# filters.net
KiCad netlist of a schematic drawn in Altium Designer
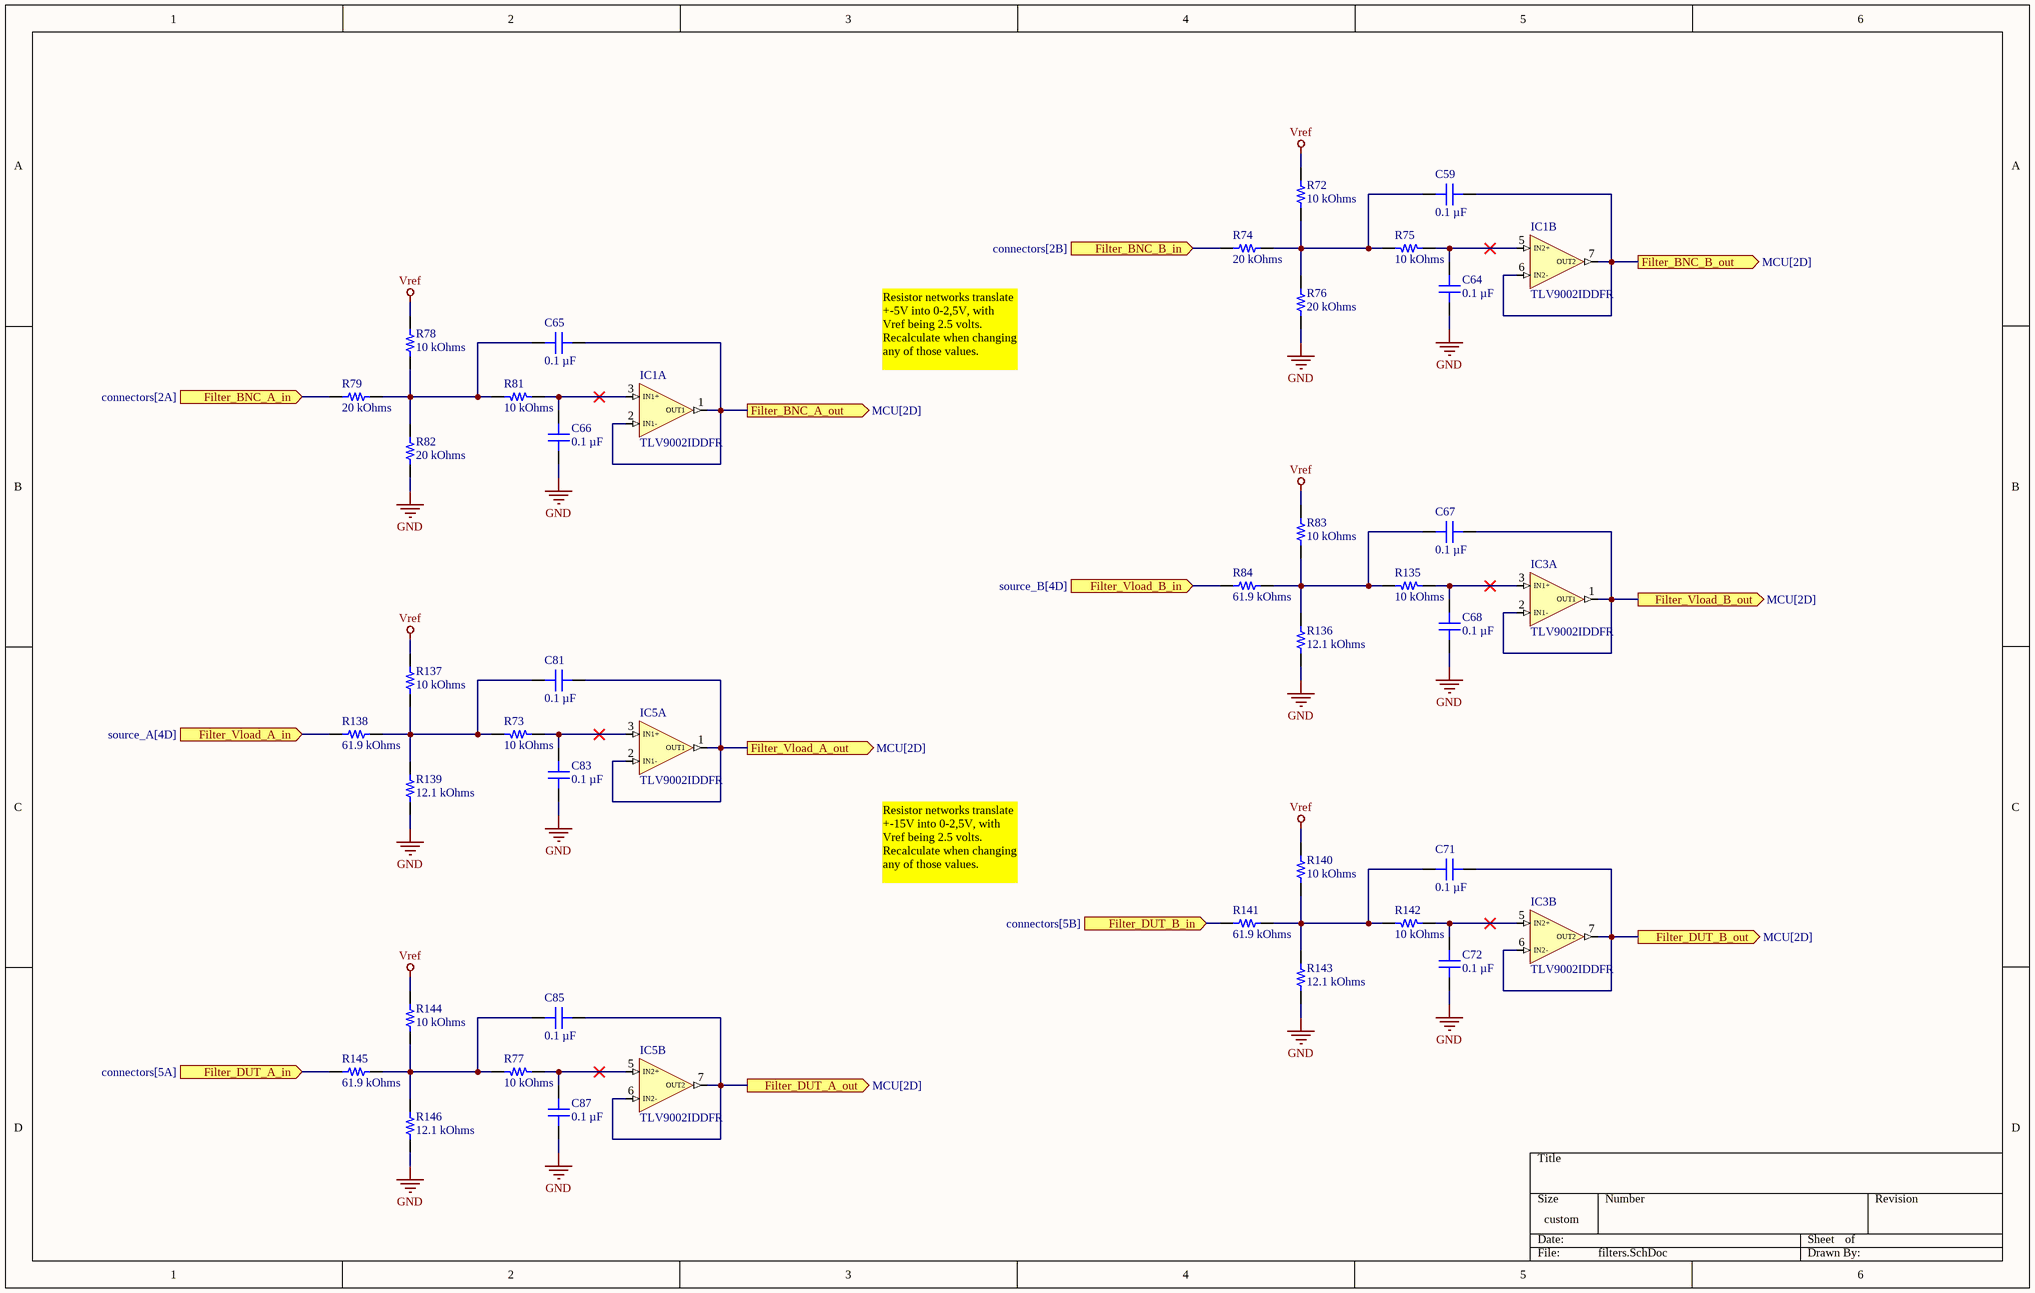
[diagram p0: filters.SchDoc]

(export (version "E")
  (design (tool "Eeschema 10.0.6"))
  (components
    (comp (ref "C59")
      (value "0.1 µF")
      (footprint "CAP 1206_3216 - 0.8MM")
      (description "CAP CER 0.1UF 50V X7R 1206")
      (fields
        (field (name "PART NUMBER") "885012208087")
        (field (name "CAPACITANCE") "0.1 µF")
        (field (name "MANUFACTURER") "Würth Elektronik")
      )
      (libsource (lib "Celestial Altium Library - altium_library") (part "Capacitor"))
    )
    (comp (ref "C64")
      (value "0.1 µF")
      (footprint "CAP 1206_3216 - 0.8MM")
      (description "CAP CER 0.1UF 50V X7R 1206")
      (fields
        (field (name "PART NUMBER") "885012208087")
        (field (name "CAPACITANCE") "0.1 µF")
        (field (name "MANUFACTURER") "Würth Elektronik")
      )
      (libsource (lib "Celestial Altium Library - altium_library") (part "Capacitor"))
    )
    (comp (ref "C65")
      (value "0.1 µF")
      (footprint "CAP 1206_3216 - 0.8MM")
      (description "CAP CER 0.1UF 50V X7R 1206")
      (fields
        (field (name "PART NUMBER") "885012208087")
        (field (name "CAPACITANCE") "0.1 µF")
        (field (name "MANUFACTURER") "Würth Elektronik")
      )
      (libsource (lib "Celestial Altium Library - altium_library") (part "Capacitor"))
    )
    (comp (ref "C66")
      (value "0.1 µF")
      (footprint "CAP 1206_3216 - 0.8MM")
      (description "CAP CER 0.1UF 50V X7R 1206")
      (fields
        (field (name "PART NUMBER") "885012208087")
        (field (name "CAPACITANCE") "0.1 µF")
        (field (name "MANUFACTURER") "Würth Elektronik")
      )
      (libsource (lib "Celestial Altium Library - altium_library") (part "Capacitor"))
    )
    (comp (ref "C67")
      (value "0.1 µF")
      (footprint "CAP 1206_3216 - 0.8MM")
      (description "CAP CER 0.1UF 50V X7R 1206")
      (fields
        (field (name "PART NUMBER") "885012208087")
        (field (name "CAPACITANCE") "0.1 µF")
        (field (name "MANUFACTURER") "Würth Elektronik")
      )
      (libsource (lib "Celestial Altium Library - altium_library") (part "Capacitor"))
    )
    (comp (ref "C68")
      (value "0.1 µF")
      (footprint "CAP 1206_3216 - 0.8MM")
      (description "CAP CER 0.1UF 50V X7R 1206")
      (fields
        (field (name "PART NUMBER") "885012208087")
        (field (name "CAPACITANCE") "0.1 µF")
        (field (name "MANUFACTURER") "Würth Elektronik")
      )
      (libsource (lib "Celestial Altium Library - altium_library") (part "Capacitor"))
    )
    (comp (ref "C71")
      (value "0.1 µF")
      (footprint "CAP 1206_3216 - 0.8MM")
      (description "CAP CER 0.1UF 50V X7R 1206")
      (fields
        (field (name "PART NUMBER") "885012208087")
        (field (name "CAPACITANCE") "0.1 µF")
        (field (name "MANUFACTURER") "Würth Elektronik")
      )
      (libsource (lib "Celestial Altium Library - altium_library") (part "Capacitor"))
    )
    (comp (ref "C72")
      (value "0.1 µF")
      (footprint "CAP 1206_3216 - 0.8MM")
      (description "CAP CER 0.1UF 50V X7R 1206")
      (fields
        (field (name "PART NUMBER") "885012208087")
        (field (name "CAPACITANCE") "0.1 µF")
        (field (name "MANUFACTURER") "Würth Elektronik")
      )
      (libsource (lib "Celestial Altium Library - altium_library") (part "Capacitor"))
    )
    (comp (ref "C81")
      (value "0.1 µF")
      (footprint "CAP 1206_3216 - 0.8MM")
      (description "CAP CER 0.1UF 50V X7R 1206")
      (fields
        (field (name "PART NUMBER") "885012208087")
        (field (name "CAPACITANCE") "0.1 µF")
        (field (name "MANUFACTURER") "Würth Elektronik")
      )
      (libsource (lib "Celestial Altium Library - altium_library") (part "Capacitor"))
    )
    (comp (ref "C83")
      (value "0.1 µF")
      (footprint "CAP 1206_3216 - 0.8MM")
      (description "CAP CER 0.1UF 50V X7R 1206")
      (fields
        (field (name "PART NUMBER") "885012208087")
        (field (name "CAPACITANCE") "0.1 µF")
        (field (name "MANUFACTURER") "Würth Elektronik")
      )
      (libsource (lib "Celestial Altium Library - altium_library") (part "Capacitor"))
    )
    (comp (ref "C85")
      (value "0.1 µF")
      (footprint "CAP 1206_3216 - 0.8MM")
      (description "CAP CER 0.1UF 50V X7R 1206")
      (fields
        (field (name "PART NUMBER") "885012208087")
        (field (name "CAPACITANCE") "0.1 µF")
        (field (name "MANUFACTURER") "Würth Elektronik")
      )
      (libsource (lib "Celestial Altium Library - altium_library") (part "Capacitor"))
    )
    (comp (ref "C87")
      (value "0.1 µF")
      (footprint "CAP 1206_3216 - 0.8MM")
      (description "CAP CER 0.1UF 50V X7R 1206")
      (fields
        (field (name "PART NUMBER") "885012208087")
        (field (name "CAPACITANCE") "0.1 µF")
        (field (name "MANUFACTURER") "Würth Elektronik")
      )
      (libsource (lib "Celestial Altium Library - altium_library") (part "Capacitor"))
    )
    (comp (ref "IC1")
      (value "TLV9002IDDFR")
      (footprint "SOT65P280X110-8N")
      (description "Integrated Circuit")
      (fields (field (name "MOUSER PART NUMBER") "595-TLV9002IDDFR"))
      (libsource (lib "za_koncar") (part "TLV9002IDDFR"))
    )
    (comp (ref "IC3")
      (value "TLV9002IDDFR")
      (footprint "SOT65P280X110-8N")
      (description "Integrated Circuit")
      (fields (field (name "MOUSER PART NUMBER") "595-TLV9002IDDFR"))
      (libsource (lib "za_koncar") (part "TLV9002IDDFR"))
    )
    (comp (ref "IC5")
      (value "TLV9002IDDFR")
      (footprint "SOT65P280X110-8N")
      (description "Integrated Circuit")
      (fields (field (name "MOUSER PART NUMBER") "595-TLV9002IDDFR"))
      (libsource (lib "za_koncar") (part "TLV9002IDDFR"))
    )
    (comp (ref "R72")
      (value "10 kOhms")
      (footprint "RES 1206_3216")
      (description "RES SMD 10K OHM 0.1% 1/4W 1206")
      (fields
        (field (name "PART NUMBER") "ERA-8AEB103V")
        (field (name "MANUFACTURER") "Panasonic Electronic Components")
      )
      (libsource (lib "Celestial Altium Library - altium_library") (part "Resistor"))
    )
    (comp (ref "R73")
      (value "10 kOhms")
      (footprint "YAGEO RES 1206_3216")
      (description "RES SMD 10K OHM 1% 1/4W 1206")
      (fields (field (name "PART NUMBER") "RT1206FRE0710KL") (field (name "MANUFACTURER") "Yageo"))
      (libsource (lib "Celestial Altium Library - altium_library") (part "Resistor"))
    )
    (comp (ref "R74")
      (value "20 kOhms")
      (footprint "RES 1206_3216")
      (description "RES SMD 20K OHM 0.1% 1/4W 1206")
      (fields
        (field (name "PART NUMBER") "ERA-8AEB203V")
        (field (name "MANUFACTURER") "Panasonic Electronic Components")
      )
      (libsource (lib "Celestial Altium Library - altium_library") (part "Resistor"))
    )
    (comp (ref "R75")
      (value "10 kOhms")
      (footprint "YAGEO RES 1206_3216")
      (description "RES SMD 10K OHM 1% 1/4W 1206")
      (fields (field (name "PART NUMBER") "RT1206FRE0710KL") (field (name "MANUFACTURER") "Yageo"))
      (libsource (lib "Celestial Altium Library - altium_library") (part "Resistor"))
    )
    (comp (ref "R76")
      (value "20 kOhms")
      (footprint "RES 1206_3216")
      (description "RES SMD 20K OHM 0.1% 1/4W 1206")
      (fields
        (field (name "PART NUMBER") "ERA-8AEB203V")
        (field (name "MANUFACTURER") "Panasonic Electronic Components")
      )
      (libsource (lib "Celestial Altium Library - altium_library") (part "Resistor"))
    )
    (comp (ref "R77")
      (value "10 kOhms")
      (footprint "YAGEO RES 1206_3216")
      (description "RES SMD 10K OHM 1% 1/4W 1206")
      (fields (field (name "PART NUMBER") "RT1206FRE0710KL") (field (name "MANUFACTURER") "Yageo"))
      (libsource (lib "Celestial Altium Library - altium_library") (part "Resistor"))
    )
    (comp (ref "R78")
      (value "10 kOhms")
      (footprint "RES 1206_3216")
      (description "RES SMD 10K OHM 0.1% 1/4W 1206")
      (fields
        (field (name "PART NUMBER") "ERA-8AEB103V")
        (field (name "MANUFACTURER") "Panasonic Electronic Components")
      )
      (libsource (lib "Celestial Altium Library - altium_library") (part "Resistor"))
    )
    (comp (ref "R79")
      (value "20 kOhms")
      (footprint "RES 1206_3216")
      (description "RES SMD 20K OHM 0.1% 1/4W 1206")
      (fields
        (field (name "PART NUMBER") "ERA-8AEB203V")
        (field (name "MANUFACTURER") "Panasonic Electronic Components")
      )
      (libsource (lib "Celestial Altium Library - altium_library") (part "Resistor"))
    )
    (comp (ref "R81")
      (value "10 kOhms")
      (footprint "YAGEO RES 1206_3216")
      (description "RES SMD 10K OHM 1% 1/4W 1206")
      (fields (field (name "PART NUMBER") "RT1206FRE0710KL") (field (name "MANUFACTURER") "Yageo"))
      (libsource (lib "Celestial Altium Library - altium_library") (part "Resistor"))
    )
    (comp (ref "R82")
      (value "20 kOhms")
      (footprint "RES 1206_3216")
      (description "RES SMD 20K OHM 0.1% 1/4W 1206")
      (fields
        (field (name "PART NUMBER") "ERA-8AEB203V")
        (field (name "MANUFACTURER") "Panasonic Electronic Components")
      )
      (libsource (lib "Celestial Altium Library - altium_library") (part "Resistor"))
    )
    (comp (ref "R83")
      (value "10 kOhms")
      (footprint "RES 1206_3216")
      (description "RES SMD 10K OHM 0.1% 1/4W 1206")
      (fields
        (field (name "PART NUMBER") "ERA-8AEB103V")
        (field (name "MANUFACTURER") "Panasonic Electronic Components")
      )
      (libsource (lib "Celestial Altium Library - altium_library") (part "Resistor"))
    )
    (comp (ref "R84")
      (value "61.9 kOhms")
      (footprint "RES 1206_3216")
      (description "RES SMD 61.9K OHM 0.1% 1/4W 1206")
      (fields
        (field (name "PART NUMBER") "ERA-8AEB6192V")
        (field (name "MANUFACTURER") "Panasonic Electronic Components")
      )
      (libsource (lib "Celestial Altium Library - altium_library") (part "Resistor"))
    )
    (comp (ref "R135")
      (value "10 kOhms")
      (footprint "YAGEO RES 1206_3216")
      (description "RES SMD 10K OHM 1% 1/4W 1206")
      (fields (field (name "PART NUMBER") "RT1206FRE0710KL") (field (name "MANUFACTURER") "Yageo"))
      (libsource (lib "Celestial Altium Library - altium_library") (part "Resistor"))
    )
    (comp (ref "R136")
      (value "12.1 kOhms")
      (footprint "RES 1206_3216")
      (description "RES SMD 12.1K OHM 0.1% 1/4W 1206")
      (fields
        (field (name "PART NUMBER") "ERA-8AEB1212V")
        (field (name "MANUFACTURER") "Panasonic Electronic Components")
      )
      (libsource (lib "Celestial Altium Library - altium_library") (part "Resistor"))
    )
    (comp (ref "R137")
      (value "10 kOhms")
      (footprint "RES 1206_3216")
      (description "RES SMD 10K OHM 0.1% 1/4W 1206")
      (fields
        (field (name "PART NUMBER") "ERA-8AEB103V")
        (field (name "MANUFACTURER") "Panasonic Electronic Components")
      )
      (libsource (lib "Celestial Altium Library - altium_library") (part "Resistor"))
    )
    (comp (ref "R138")
      (value "61.9 kOhms")
      (footprint "RES 1206_3216")
      (description "RES SMD 61.9K OHM 0.1% 1/4W 1206")
      (fields
        (field (name "PART NUMBER") "ERA-8AEB6192V")
        (field (name "MANUFACTURER") "Panasonic Electronic Components")
      )
      (libsource (lib "Celestial Altium Library - altium_library") (part "Resistor"))
    )
    (comp (ref "R139")
      (value "12.1 kOhms")
      (footprint "RES 1206_3216")
      (description "RES SMD 12.1K OHM 0.1% 1/4W 1206")
      (fields
        (field (name "PART NUMBER") "ERA-8AEB1212V")
        (field (name "MANUFACTURER") "Panasonic Electronic Components")
      )
      (libsource (lib "Celestial Altium Library - altium_library") (part "Resistor"))
    )
    (comp (ref "R140")
      (value "10 kOhms")
      (footprint "RES 1206_3216")
      (description "RES SMD 10K OHM 0.1% 1/4W 1206")
      (fields
        (field (name "PART NUMBER") "ERA-8AEB103V")
        (field (name "MANUFACTURER") "Panasonic Electronic Components")
      )
      (libsource (lib "Celestial Altium Library - altium_library") (part "Resistor"))
    )
    (comp (ref "R141")
      (value "61.9 kOhms")
      (footprint "RES 1206_3216")
      (description "RES SMD 61.9K OHM 0.1% 1/4W 1206")
      (fields
        (field (name "PART NUMBER") "ERA-8AEB6192V")
        (field (name "MANUFACTURER") "Panasonic Electronic Components")
      )
      (libsource (lib "Celestial Altium Library - altium_library") (part "Resistor"))
    )
    (comp (ref "R142")
      (value "10 kOhms")
      (footprint "YAGEO RES 1206_3216")
      (description "RES SMD 10K OHM 1% 1/4W 1206")
      (fields (field (name "PART NUMBER") "RT1206FRE0710KL") (field (name "MANUFACTURER") "Yageo"))
      (libsource (lib "Celestial Altium Library - altium_library") (part "Resistor"))
    )
    (comp (ref "R143")
      (value "12.1 kOhms")
      (footprint "RES 1206_3216")
      (description "RES SMD 12.1K OHM 0.1% 1/4W 1206")
      (fields
        (field (name "PART NUMBER") "ERA-8AEB1212V")
        (field (name "MANUFACTURER") "Panasonic Electronic Components")
      )
      (libsource (lib "Celestial Altium Library - altium_library") (part "Resistor"))
    )
    (comp (ref "R144")
      (value "10 kOhms")
      (footprint "RES 1206_3216")
      (description "RES SMD 10K OHM 0.1% 1/4W 1206")
      (fields
        (field (name "PART NUMBER") "ERA-8AEB103V")
        (field (name "MANUFACTURER") "Panasonic Electronic Components")
      )
      (libsource (lib "Celestial Altium Library - altium_library") (part "Resistor"))
    )
    (comp (ref "R145")
      (value "61.9 kOhms")
      (footprint "RES 1206_3216")
      (description "RES SMD 61.9K OHM 0.1% 1/4W 1206")
      (fields
        (field (name "PART NUMBER") "ERA-8AEB6192V")
        (field (name "MANUFACTURER") "Panasonic Electronic Components")
      )
      (libsource (lib "Celestial Altium Library - altium_library") (part "Resistor"))
    )
    (comp (ref "R146")
      (value "12.1 kOhms")
      (footprint "RES 1206_3216")
      (description "RES SMD 12.1K OHM 0.1% 1/4W 1206")
      (fields
        (field (name "PART NUMBER") "ERA-8AEB1212V")
        (field (name "MANUFACTURER") "Panasonic Electronic Components")
      )
      (libsource (lib "Celestial Altium Library - altium_library") (part "Resistor"))
    )
  )
  (nets
    (net (code "1") (name "/Filter_BNC_A_in") (class "Default")
      (node (ref "R79") (pin "1") (pinfunction "1_1") (pintype "passive"))
    )
    (net (code "2") (name "/Filter_BNC_A_out") (class "Default")
      (node (ref "C65") (pin "1") (pinfunction "1_1") (pintype "passive"))
      (node (ref "IC1") (pin "1") (pinfunction "OUT1_1") (pintype "output"))
      (node (ref "IC1") (pin "2") (pinfunction "IN1-_2") (pintype "input"))
    )
    (net (code "3") (name "/Filter_BNC_B_in") (class "Default")
      (node (ref "R74") (pin "1") (pinfunction "1_1") (pintype "passive"))
    )
    (net (code "4") (name "/Filter_BNC_B_out") (class "Default")
      (node (ref "C59") (pin "1") (pinfunction "1_1") (pintype "passive"))
      (node (ref "IC1") (pin "6") (pinfunction "IN2-_6") (pintype "input"))
      (node (ref "IC1") (pin "7") (pinfunction "OUT2_7") (pintype "output"))
    )
    (net (code "5") (name "/Filter_DUT_A_in") (class "Default")
      (node (ref "R145") (pin "1") (pinfunction "1_1") (pintype "passive"))
    )
    (net (code "6") (name "/Filter_DUT_A_out") (class "Default")
      (node (ref "C85") (pin "1") (pinfunction "1_1") (pintype "passive"))
      (node (ref "IC5") (pin "6") (pinfunction "IN2-_6") (pintype "input"))
      (node (ref "IC5") (pin "7") (pinfunction "OUT2_7") (pintype "output"))
    )
    (net (code "7") (name "/Filter_DUT_B_in") (class "Default")
      (node (ref "R141") (pin "1") (pinfunction "1_1") (pintype "passive"))
    )
    (net (code "8") (name "/Filter_DUT_B_out") (class "Default")
      (node (ref "C71") (pin "1") (pinfunction "1_1") (pintype "passive"))
      (node (ref "IC3") (pin "6") (pinfunction "IN2-_6") (pintype "input"))
      (node (ref "IC3") (pin "7") (pinfunction "OUT2_7") (pintype "output"))
    )
    (net (code "9") (name "/Filter_Vload_A_in") (class "Default")
      (node (ref "R138") (pin "1") (pinfunction "1_1") (pintype "passive"))
    )
    (net (code "10") (name "/Filter_Vload_A_out") (class "Default")
      (node (ref "C81") (pin "1") (pinfunction "1_1") (pintype "passive"))
      (node (ref "IC5") (pin "1") (pinfunction "OUT1_1") (pintype "output"))
      (node (ref "IC5") (pin "2") (pinfunction "IN1-_2") (pintype "input"))
    )
    (net (code "11") (name "/Filter_Vload_B_in") (class "Default")
      (node (ref "R84") (pin "1") (pinfunction "1_1") (pintype "passive"))
    )
    (net (code "12") (name "/Filter_Vload_B_out") (class "Default")
      (node (ref "C67") (pin "1") (pinfunction "1_1") (pintype "passive"))
      (node (ref "IC3") (pin "1") (pinfunction "OUT1_1") (pintype "output"))
      (node (ref "IC3") (pin "2") (pinfunction "IN1-_2") (pintype "input"))
    )
    (net (code "13") (name "GND") (class "Default")
      (node (ref "C64") (pin "2") (pinfunction "2_2") (pintype "passive"))
      (node (ref "C66") (pin "2") (pinfunction "2_2") (pintype "passive"))
      (node (ref "C68") (pin "2") (pinfunction "2_2") (pintype "passive"))
      (node (ref "C72") (pin "2") (pinfunction "2_2") (pintype "passive"))
      (node (ref "C83") (pin "2") (pinfunction "2_2") (pintype "passive"))
      (node (ref "C87") (pin "2") (pinfunction "2_2") (pintype "passive"))
      (node (ref "R136") (pin "2") (pinfunction "2_2") (pintype "passive"))
      (node (ref "R139") (pin "2") (pinfunction "2_2") (pintype "passive"))
      (node (ref "R143") (pin "2") (pinfunction "2_2") (pintype "passive"))
      (node (ref "R146") (pin "2") (pinfunction "2_2") (pintype "passive"))
      (node (ref "R76") (pin "2") (pinfunction "2_2") (pintype "passive"))
      (node (ref "R82") (pin "2") (pinfunction "2_2") (pintype "passive"))
    )
    (net (code "14") (name "Net-(C59-Pad2)") (class "Default")
      (node (ref "C59") (pin "2") (pinfunction "2_2") (pintype "passive"))
      (node (ref "R72") (pin "2") (pinfunction "2_2") (pintype "passive"))
      (node (ref "R74") (pin "2") (pinfunction "2_2") (pintype "passive"))
      (node (ref "R75") (pin "2") (pinfunction "2_2") (pintype "passive"))
      (node (ref "R76") (pin "1") (pinfunction "1_1") (pintype "passive"))
    )
    (net (code "15") (name "Net-(C65-Pad2)") (class "Default")
      (node (ref "C65") (pin "2") (pinfunction "2_2") (pintype "passive"))
      (node (ref "R78") (pin "2") (pinfunction "2_2") (pintype "passive"))
      (node (ref "R79") (pin "2") (pinfunction "2_2") (pintype "passive"))
      (node (ref "R81") (pin "2") (pinfunction "2_2") (pintype "passive"))
      (node (ref "R82") (pin "1") (pinfunction "1_1") (pintype "passive"))
    )
    (net (code "16") (name "Net-(C67-Pad2)") (class "Default")
      (node (ref "C67") (pin "2") (pinfunction "2_2") (pintype "passive"))
      (node (ref "R135") (pin "2") (pinfunction "2_2") (pintype "passive"))
      (node (ref "R136") (pin "1") (pinfunction "1_1") (pintype "passive"))
      (node (ref "R83") (pin "2") (pinfunction "2_2") (pintype "passive"))
      (node (ref "R84") (pin "2") (pinfunction "2_2") (pintype "passive"))
    )
    (net (code "17") (name "Net-(C71-Pad2)") (class "Default")
      (node (ref "C71") (pin "2") (pinfunction "2_2") (pintype "passive"))
      (node (ref "R140") (pin "2") (pinfunction "2_2") (pintype "passive"))
      (node (ref "R141") (pin "2") (pinfunction "2_2") (pintype "passive"))
      (node (ref "R142") (pin "2") (pinfunction "2_2") (pintype "passive"))
      (node (ref "R143") (pin "1") (pinfunction "1_1") (pintype "passive"))
    )
    (net (code "18") (name "Net-(C81-Pad2)") (class "Default")
      (node (ref "C81") (pin "2") (pinfunction "2_2") (pintype "passive"))
      (node (ref "R137") (pin "2") (pinfunction "2_2") (pintype "passive"))
      (node (ref "R138") (pin "2") (pinfunction "2_2") (pintype "passive"))
      (node (ref "R139") (pin "1") (pinfunction "1_1") (pintype "passive"))
      (node (ref "R73") (pin "2") (pinfunction "2_2") (pintype "passive"))
    )
    (net (code "19") (name "Net-(C85-Pad2)") (class "Default")
      (node (ref "C85") (pin "2") (pinfunction "2_2") (pintype "passive"))
      (node (ref "R144") (pin "2") (pinfunction "2_2") (pintype "passive"))
      (node (ref "R145") (pin "2") (pinfunction "2_2") (pintype "passive"))
      (node (ref "R146") (pin "1") (pinfunction "1_1") (pintype "passive"))
      (node (ref "R77") (pin "2") (pinfunction "2_2") (pintype "passive"))
    )
    (net (code "20") (name "Net-(IC1A-IN1+)") (class "Default")
      (node (ref "C66") (pin "1") (pinfunction "1_1") (pintype "passive"))
      (node (ref "IC1") (pin "3") (pinfunction "IN1+_3") (pintype "input"))
      (node (ref "R81") (pin "1") (pinfunction "1_1") (pintype "passive"))
    )
    (net (code "21") (name "Net-(IC1B-IN2+)") (class "Default")
      (node (ref "C64") (pin "1") (pinfunction "1_1") (pintype "passive"))
      (node (ref "IC1") (pin "5") (pinfunction "IN2+_5") (pintype "input"))
      (node (ref "R75") (pin "1") (pinfunction "1_1") (pintype "passive"))
    )
    (net (code "22") (name "Net-(IC3A-IN1+)") (class "Default")
      (node (ref "C68") (pin "1") (pinfunction "1_1") (pintype "passive"))
      (node (ref "IC3") (pin "3") (pinfunction "IN1+_3") (pintype "input"))
      (node (ref "R135") (pin "1") (pinfunction "1_1") (pintype "passive"))
    )
    (net (code "23") (name "Net-(IC3B-IN2+)") (class "Default")
      (node (ref "C72") (pin "1") (pinfunction "1_1") (pintype "passive"))
      (node (ref "IC3") (pin "5") (pinfunction "IN2+_5") (pintype "input"))
      (node (ref "R142") (pin "1") (pinfunction "1_1") (pintype "passive"))
    )
    (net (code "24") (name "Net-(IC5A-IN1+)") (class "Default")
      (node (ref "C83") (pin "1") (pinfunction "1_1") (pintype "passive"))
      (node (ref "IC5") (pin "3") (pinfunction "IN1+_3") (pintype "input"))
      (node (ref "R73") (pin "1") (pinfunction "1_1") (pintype "passive"))
    )
    (net (code "25") (name "Net-(IC5B-IN2+)") (class "Default")
      (node (ref "C87") (pin "1") (pinfunction "1_1") (pintype "passive"))
      (node (ref "IC5") (pin "5") (pinfunction "IN2+_5") (pintype "input"))
      (node (ref "R77") (pin "1") (pinfunction "1_1") (pintype "passive"))
    )
    (net (code "26") (name "Vref") (class "Default")
      (node (ref "R137") (pin "1") (pinfunction "1_1") (pintype "passive"))
      (node (ref "R140") (pin "1") (pinfunction "1_1") (pintype "passive"))
      (node (ref "R144") (pin "1") (pinfunction "1_1") (pintype "passive"))
      (node (ref "R72") (pin "1") (pinfunction "1_1") (pintype "passive"))
      (node (ref "R78") (pin "1") (pinfunction "1_1") (pintype "passive"))
      (node (ref "R83") (pin "1") (pinfunction "1_1") (pintype "passive"))
    )
  )
)
